# GiGaMega_uneversal_1.net
KiCad netlist of a schematic drawn in EAGLE
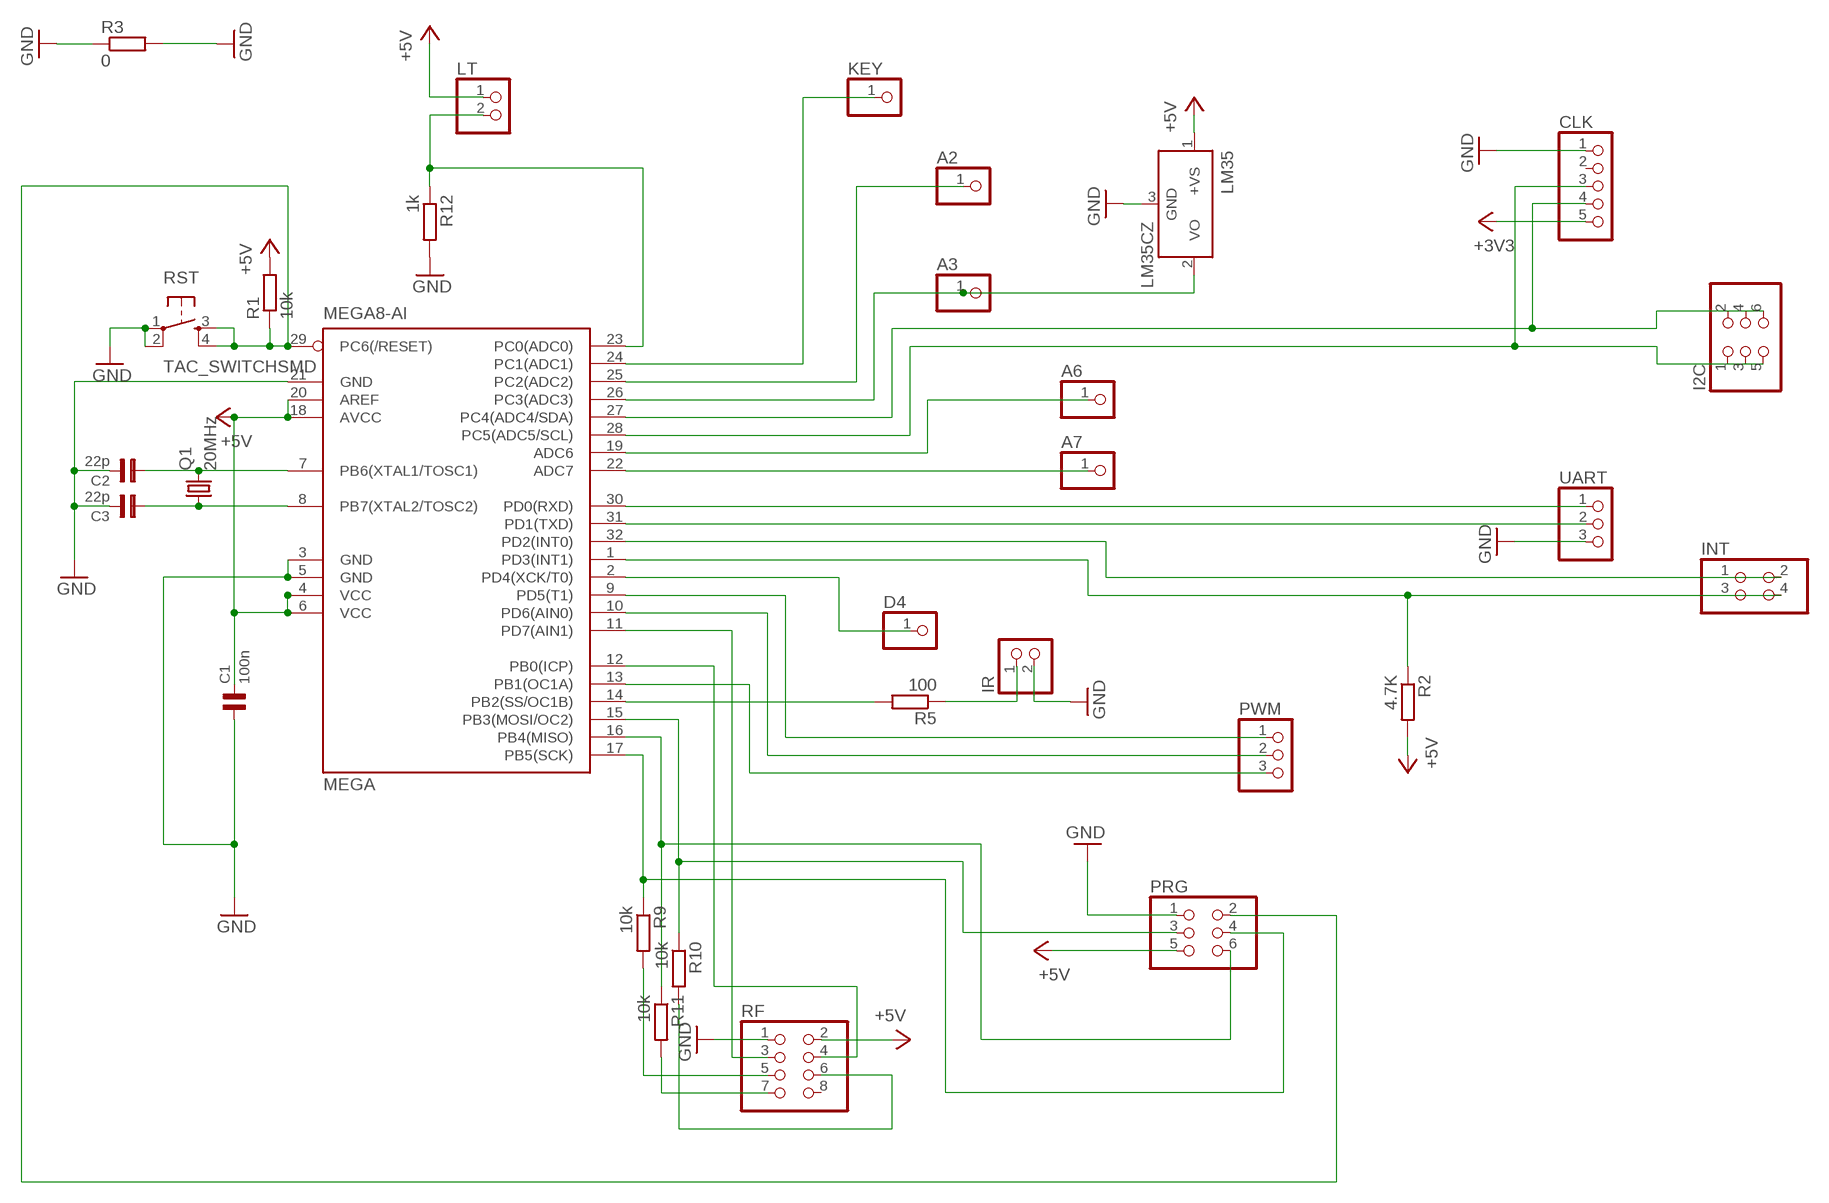
[diagram p0: schematic, sheet 1]
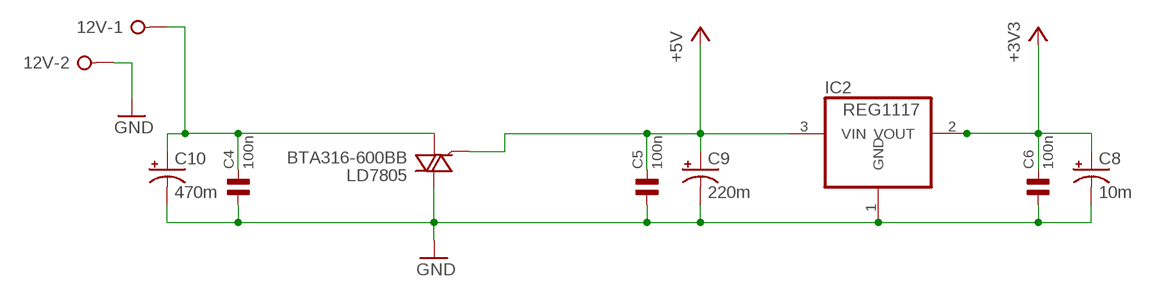
[diagram p1: schematic, sheet 2]

(export (version "E")
  (design (tool "Eeschema 10.0.6"))
  (components
    (comp (ref "12V")
      (value "W237-02P")
      (footprint "eagle-import:W237-132")
      (libsource (lib "eagle-import") (part "W237-02P"))
    )
    (comp (ref "C4")
      (value "100n")
      (footprint "eagle-import:1206")
      (libsource (lib "eagle-import") (part "C1206"))
    )
    (comp (ref "C5")
      (value "100n")
      (footprint "eagle-import:1206")
      (libsource (lib "eagle-import") (part "C1206"))
    )
    (comp (ref "C6")
      (value "100n")
      (footprint "eagle-import:1206")
      (libsource (lib "eagle-import") (part "C1206"))
    )
    (comp (ref "C8")
      (value "10m")
      (footprint "eagle-import:UD-4X5,8_NICHICON")
      (libsource (lib "eagle-import") (part "CPOL-USUD-4X5,8"))
    )
    (comp (ref "C9")
      (value "220m")
      (footprint "eagle-import:UD-6,3X7,7_NICHICON")
      (libsource (lib "eagle-import") (part "CPOL-USUD-6,3X7,7"))
    )
    (comp (ref "C10")
      (value "470m")
      (footprint "eagle-import:UD-10X10_NICHICON")
      (libsource (lib "eagle-import") (part "CPOL-USUD-10X10"))
    )
    (comp (ref "IC2")
      (value "REG1117")
      (footprint "eagle-import:SOT223")
      (libsource (lib "eagle-import") (part "REG1117"))
    )
    (comp (ref "LD7805")
      (value "BTA316-600BB")
      (footprint "eagle-import:SOT404")
      (libsource (lib "eagle-import") (part "BTA316B-600B"))
    )
    (comp (ref "A2")
      (value "PINHD-1X1")
      (footprint "eagle-import:1X01")
      (libsource (lib "eagle-import") (part "PINHD-1X1"))
    )
    (comp (ref "A3")
      (value "PINHD-1X1")
      (footprint "eagle-import:1X01")
      (libsource (lib "eagle-import") (part "PINHD-1X1"))
    )
    (comp (ref "A6")
      (value "PINHD-1X1")
      (footprint "eagle-import:1X01")
      (libsource (lib "eagle-import") (part "PINHD-1X1"))
    )
    (comp (ref "A7")
      (value "PINHD-1X1")
      (footprint "eagle-import:1X01")
      (libsource (lib "eagle-import") (part "PINHD-1X1"))
    )
    (comp (ref "C1")
      (value "100n")
      (footprint "eagle-import:1206")
      (libsource (lib "eagle-import") (part "C1206"))
    )
    (comp (ref "C2")
      (value "22p")
      (footprint "eagle-import:1206")
      (libsource (lib "eagle-import") (part "C1206"))
    )
    (comp (ref "C3")
      (value "22p")
      (footprint "eagle-import:1206")
      (libsource (lib "eagle-import") (part "C1206"))
    )
    (comp (ref "CLK")
      (value "PINHD-1X5")
      (footprint "eagle-import:1X05")
      (libsource (lib "eagle-import") (part "PINHD-1X5"))
    )
    (comp (ref "D4")
      (value "PINHD-1X1")
      (footprint "eagle-import:1X01")
      (libsource (lib "eagle-import") (part "PINHD-1X1"))
    )
    (comp (ref "I2C")
      (value "PINHD-2X3")
      (footprint "eagle-import:2X03")
      (libsource (lib "eagle-import") (part "PINHD-2X3"))
    )
    (comp (ref "INT")
      (value "PINHD-2X2")
      (footprint "eagle-import:2X02")
      (libsource (lib "eagle-import") (part "PINHD-2X2"))
    )
    (comp (ref "IR")
      (value "PINHD-1X2")
      (footprint "eagle-import:1X02")
      (libsource (lib "eagle-import") (part "PINHD-1X2"))
    )
    (comp (ref "KEY")
      (value "PINHD-1X1")
      (footprint "eagle-import:1X01")
      (libsource (lib "eagle-import") (part "PINHD-1X1"))
    )
    (comp (ref "LM35")
      (value "LM35CZ")
      (footprint "eagle-import:TO92")
      (libsource (lib "eagle-import") (part "LM35CZ"))
    )
    (comp (ref "LT")
      (value "PINHD-1X2")
      (footprint "eagle-import:1X02")
      (libsource (lib "eagle-import") (part "PINHD-1X2"))
    )
    (comp (ref "MEGA")
      (value "MEGA8-AI")
      (footprint "eagle-import:TQFP32-08")
      (fields (field (name "MPN") "ATMEGA8-16AU"))
      (libsource (lib "eagle-import") (part "MEGA8-AI"))
    )
    (comp (ref "PRG")
      (value "PINHD-2X3")
      (footprint "eagle-import:2X03")
      (libsource (lib "eagle-import") (part "PINHD-2X3"))
    )
    (comp (ref "PWM")
      (value "PINHD-1X3")
      (footprint "eagle-import:1X03")
      (libsource (lib "eagle-import") (part "PINHD-1X3"))
    )
    (comp (ref "Q1")
      (value "20MHz")
      (footprint "eagle-import:HC49UP")
      (libsource (lib "eagle-import") (part "CRYSTALHC49UP"))
    )
    (comp (ref "R1")
      (value "10k")
      (footprint "eagle-import:R1206")
      (libsource (lib "eagle-import") (part "R-EU_R1206"))
    )
    (comp (ref "R2")
      (value "4.7K")
      (footprint "eagle-import:R1206")
      (libsource (lib "eagle-import") (part "R-EU_R1206"))
    )
    (comp (ref "R3")
      (value "0")
      (footprint "eagle-import:R1206")
      (libsource (lib "eagle-import") (part "R-EU_R1206"))
    )
    (comp (ref "R5")
      (value "100")
      (footprint "eagle-import:R1206")
      (libsource (lib "eagle-import") (part "R-EU_R1206"))
    )
    (comp (ref "R9")
      (value "10k")
      (footprint "eagle-import:R1206")
      (libsource (lib "eagle-import") (part "R-EU_R1206"))
    )
    (comp (ref "R10")
      (value "10k")
      (footprint "eagle-import:R1206")
      (libsource (lib "eagle-import") (part "R-EU_R1206"))
    )
    (comp (ref "R11")
      (value "10k")
      (footprint "eagle-import:R1206")
      (libsource (lib "eagle-import") (part "R-EU_R1206"))
    )
    (comp (ref "R12")
      (value "1k")
      (footprint "eagle-import:R1206")
      (libsource (lib "eagle-import") (part "R-EU_R1206"))
    )
    (comp (ref "RF")
      (value "PINHD-2X4")
      (footprint "eagle-import:2X04")
      (libsource (lib "eagle-import") (part "PINHD-2X4"))
    )
    (comp (ref "RST")
      (value "TAC_SWITCHSMD")
      (footprint "eagle-import:TACTILE-SWITCH-SMD")
      (libsource (lib "eagle-import") (part "TAC_SWITCHSMD"))
    )
    (comp (ref "UART")
      (value "PINHD-1X3")
      (footprint "eagle-import:1X03")
      (libsource (lib "eagle-import") (part "PINHD-1X3"))
    )
  )
  (nets
    (net (code "1") (name "+3V3") (class "Default")
      (node (ref "C6") (pin "2") (pinfunction "2_2") (pintype "passive"))
      (node (ref "C8") (pin "+") (pinfunction "+_+") (pintype "passive"))
      (node (ref "CLK") (pin "5") (pinfunction "5_5") (pintype "passive"))
      (node (ref "IC2") (pin "2") (pinfunction "VOUT_2") (pintype "output"))
    )
    (net (code "2") (name "+5V") (class "Default")
      (node (ref "C1") (pin "2") (pinfunction "2_2") (pintype "passive"))
      (node (ref "C5") (pin "2") (pinfunction "2_2") (pintype "passive"))
      (node (ref "C9") (pin "+") (pinfunction "+_+") (pintype "passive"))
      (node (ref "IC2") (pin "3") (pinfunction "VIN_3") (pintype "input"))
      (node (ref "LD7805") (pin "3") (pinfunction "G_3") (pintype "passive"))
      (node (ref "LM35") (pin "1") (pinfunction "+VS_1") (pintype "input"))
      (node (ref "LT") (pin "1") (pinfunction "1_1") (pintype "passive"))
      (node (ref "MEGA") (pin "18") (pinfunction "AVCC_18") (pintype "power_in"))
      (node (ref "MEGA") (pin "20") (pinfunction "AREF_20") (pintype "passive"))
      (node (ref "MEGA") (pin "4") (pinfunction "VCC_4") (pintype "power_in"))
      (node (ref "MEGA") (pin "6") (pinfunction "VCC_6") (pintype "power_in"))
      (node (ref "PRG") (pin "5") (pinfunction "5_5") (pintype "passive"))
      (node (ref "R1") (pin "2") (pinfunction "2_2") (pintype "passive"))
      (node (ref "R2") (pin "2") (pinfunction "2_2") (pintype "passive"))
      (node (ref "RF") (pin "2") (pinfunction "2_2") (pintype "passive"))
    )
    (net (code "3") (name "GND") (class "Default")
      (node (ref "12V") (pin "2") (pinfunction "KL_2") (pintype "passive"))
      (node (ref "C1") (pin "1") (pinfunction "1_1") (pintype "passive"))
      (node (ref "C10") (pin "-") (pinfunction "-_-") (pintype "passive"))
      (node (ref "C2") (pin "2") (pinfunction "2_2") (pintype "passive"))
      (node (ref "C3") (pin "2") (pinfunction "2_2") (pintype "passive"))
      (node (ref "C4") (pin "1") (pinfunction "1_1") (pintype "passive"))
      (node (ref "C5") (pin "1") (pinfunction "1_1") (pintype "passive"))
      (node (ref "C6") (pin "1") (pinfunction "1_1") (pintype "passive"))
      (node (ref "C8") (pin "-") (pinfunction "-_-") (pintype "passive"))
      (node (ref "C9") (pin "-") (pinfunction "-_-") (pintype "passive"))
      (node (ref "CLK") (pin "1") (pinfunction "1_1") (pintype "passive"))
      (node (ref "IC2") (pin "1") (pinfunction "GND_1") (pintype "power_in"))
      (node (ref "IR") (pin "2") (pinfunction "2_2") (pintype "passive"))
      (node (ref "LD7805") (pin "MB") (pinfunction "LD_MB") (pintype "passive"))
      (node (ref "LM35") (pin "3") (pinfunction "GND_3") (pintype "power_in"))
      (node (ref "MEGA") (pin "21") (pinfunction "GND_21") (pintype "power_in"))
      (node (ref "MEGA") (pin "3") (pinfunction "GND_3") (pintype "power_in"))
      (node (ref "MEGA") (pin "5") (pinfunction "GND_5") (pintype "power_in"))
      (node (ref "PRG") (pin "1") (pinfunction "1_1") (pintype "passive"))
      (node (ref "R12") (pin "2") (pinfunction "2_2") (pintype "passive"))
      (node (ref "R3") (pin "1") (pinfunction "1_1") (pintype "passive"))
      (node (ref "R3") (pin "2") (pinfunction "2_2") (pintype "passive"))
      (node (ref "RF") (pin "1") (pinfunction "1_1") (pintype "passive"))
      (node (ref "RST") (pin "1") (pinfunction "1_1") (pintype "passive"))
      (node (ref "RST") (pin "2") (pinfunction "2_2") (pintype "passive"))
      (node (ref "UART") (pin "3") (pinfunction "3_3") (pintype "passive"))
    )
    (net (code "4") (name "Net-(12VA-KL)") (class "Default")
      (node (ref "12V") (pin "1") (pinfunction "KL_1") (pintype "passive"))
      (node (ref "C10") (pin "+") (pinfunction "+_+") (pintype "passive"))
      (node (ref "C4") (pin "2") (pinfunction "2_2") (pintype "passive"))
      (node (ref "LD7805") (pin "1") (pinfunction "CM_1") (pintype "passive"))
    )
    (net (code "5") (name "Net-(IR-Pad1)") (class "Default")
      (node (ref "IR") (pin "1") (pinfunction "1_1") (pintype "passive"))
      (node (ref "R5") (pin "1") (pinfunction "1_1") (pintype "passive"))
    )
    (net (code "6") (name "Net-(LM35-VO)") (class "Default")
      (node (ref "A3") (pin "1") (pinfunction "1_1") (pintype "passive"))
      (node (ref "LM35") (pin "2") (pinfunction "VO_2") (pintype "input"))
      (node (ref "MEGA") (pin "26") (pinfunction "PC3(ADC3)_26") (pintype "bidirectional"))
    )
    (net (code "7") (name "Net-(MEGA-ADC6)") (class "Default")
      (node (ref "A6") (pin "1") (pinfunction "1_1") (pintype "passive"))
      (node (ref "MEGA") (pin "19") (pinfunction "ADC6_19") (pintype "bidirectional"))
    )
    (net (code "8") (name "Net-(MEGA-ADC7)") (class "Default")
      (node (ref "A7") (pin "1") (pinfunction "1_1") (pintype "passive"))
      (node (ref "MEGA") (pin "22") (pinfunction "ADC7_22") (pintype "bidirectional"))
    )
    (net (code "9") (name "Net-(MEGA-PB0(ICP))") (class "Default")
      (node (ref "MEGA") (pin "12") (pinfunction "PB0(ICP)_12") (pintype "bidirectional"))
      (node (ref "RF") (pin "4") (pinfunction "4_4") (pintype "passive"))
    )
    (net (code "10") (name "Net-(MEGA-PB1(OC1A))") (class "Default")
      (node (ref "MEGA") (pin "13") (pinfunction "PB1(OC1A)_13") (pintype "bidirectional"))
      (node (ref "PWM") (pin "3") (pinfunction "3_3") (pintype "passive"))
    )
    (net (code "11") (name "Net-(MEGA-PB2(SS{slash}OC1B))") (class "Default")
      (node (ref "MEGA") (pin "14") (pinfunction "PB2(SS/OC1B)_14") (pintype "bidirectional"))
      (node (ref "R5") (pin "2") (pinfunction "2_2") (pintype "passive"))
    )
    (net (code "12") (name "Net-(MEGA-PB3(MOSI{slash}OC2))") (class "Default")
      (node (ref "MEGA") (pin "15") (pinfunction "PB3(MOSI/OC2)_15") (pintype "bidirectional"))
      (node (ref "PRG") (pin "3") (pinfunction "3_3") (pintype "passive"))
      (node (ref "R10") (pin "1") (pinfunction "1_1") (pintype "passive"))
    )
    (net (code "13") (name "Net-(MEGA-PB4(MISO))") (class "Default")
      (node (ref "MEGA") (pin "16") (pinfunction "PB4(MISO)_16") (pintype "bidirectional"))
      (node (ref "PRG") (pin "6") (pinfunction "6_6") (pintype "passive"))
      (node (ref "R11") (pin "1") (pinfunction "1_1") (pintype "passive"))
    )
    (net (code "14") (name "Net-(MEGA-PB5(SCK))") (class "Default")
      (node (ref "MEGA") (pin "17") (pinfunction "PB5(SCK)_17") (pintype "bidirectional"))
      (node (ref "PRG") (pin "4") (pinfunction "4_4") (pintype "passive"))
      (node (ref "R9") (pin "1") (pinfunction "1_1") (pintype "passive"))
    )
    (net (code "15") (name "Net-(MEGA-PB6(XTAL1{slash}TOSC1))") (class "Default")
      (node (ref "C2") (pin "1") (pinfunction "1_1") (pintype "passive"))
      (node (ref "MEGA") (pin "7") (pinfunction "PB6(XTAL1/TOSC1)_7") (pintype "bidirectional"))
      (node (ref "Q1") (pin "2") (pinfunction "2_2") (pintype "passive"))
    )
    (net (code "16") (name "Net-(MEGA-PB7(XTAL2{slash}TOSC2))") (class "Default")
      (node (ref "C3") (pin "1") (pinfunction "1_1") (pintype "passive"))
      (node (ref "MEGA") (pin "8") (pinfunction "PB7(XTAL2/TOSC2)_8") (pintype "bidirectional"))
      (node (ref "Q1") (pin "1") (pinfunction "1_1") (pintype "passive"))
    )
    (net (code "17") (name "Net-(MEGA-PC0(ADC0))") (class "Default")
      (node (ref "LT") (pin "2") (pinfunction "2_2") (pintype "passive"))
      (node (ref "MEGA") (pin "23") (pinfunction "PC0(ADC0)_23") (pintype "bidirectional"))
      (node (ref "R12") (pin "1") (pinfunction "1_1") (pintype "passive"))
    )
    (net (code "18") (name "Net-(MEGA-PC1(ADC1))") (class "Default")
      (node (ref "KEY") (pin "1") (pinfunction "1_1") (pintype "passive"))
      (node (ref "MEGA") (pin "24") (pinfunction "PC1(ADC1)_24") (pintype "bidirectional"))
    )
    (net (code "19") (name "Net-(MEGA-PC2(ADC2))") (class "Default")
      (node (ref "A2") (pin "1") (pinfunction "1_1") (pintype "passive"))
      (node (ref "MEGA") (pin "25") (pinfunction "PC2(ADC2)_25") (pintype "bidirectional"))
    )
    (net (code "20") (name "Net-(MEGA-PC4(ADC4{slash}SDA))") (class "Default")
      (node (ref "CLK") (pin "4") (pinfunction "4_4") (pintype "passive"))
      (node (ref "I2C") (pin "2") (pinfunction "2_2") (pintype "passive"))
      (node (ref "I2C") (pin "4") (pinfunction "4_4") (pintype "passive"))
      (node (ref "I2C") (pin "6") (pinfunction "6_6") (pintype "passive"))
      (node (ref "MEGA") (pin "27") (pinfunction "PC4(ADC4/SDA)_27") (pintype "bidirectional"))
    )
    (net (code "21") (name "Net-(MEGA-PC5(ADC5{slash}SCL))") (class "Default")
      (node (ref "CLK") (pin "3") (pinfunction "3_3") (pintype "passive"))
      (node (ref "I2C") (pin "1") (pinfunction "1_1") (pintype "passive"))
      (node (ref "I2C") (pin "3") (pinfunction "3_3") (pintype "passive"))
      (node (ref "I2C") (pin "5") (pinfunction "5_5") (pintype "passive"))
      (node (ref "MEGA") (pin "28") (pinfunction "PC5(ADC5/SCL)_28") (pintype "bidirectional"))
    )
    (net (code "22") (name "Net-(MEGA-PC6({slash}RESET))") (class "Default")
      (node (ref "MEGA") (pin "29") (pinfunction "PC6(/RESET)_29") (pintype "bidirectional"))
      (node (ref "PRG") (pin "2") (pinfunction "2_2") (pintype "passive"))
      (node (ref "R1") (pin "1") (pinfunction "1_1") (pintype "passive"))
      (node (ref "RST") (pin "3") (pinfunction "3_3") (pintype "passive"))
      (node (ref "RST") (pin "4") (pinfunction "4_4") (pintype "passive"))
    )
    (net (code "23") (name "Net-(MEGA-PD0(RXD))") (class "Default")
      (node (ref "MEGA") (pin "30") (pinfunction "PD0(RXD)_30") (pintype "bidirectional"))
      (node (ref "UART") (pin "1") (pinfunction "1_1") (pintype "passive"))
    )
    (net (code "24") (name "Net-(MEGA-PD1(TXD))") (class "Default")
      (node (ref "MEGA") (pin "31") (pinfunction "PD1(TXD)_31") (pintype "bidirectional"))
      (node (ref "UART") (pin "2") (pinfunction "2_2") (pintype "passive"))
    )
    (net (code "25") (name "Net-(MEGA-PD2(INT0))") (class "Default")
      (node (ref "INT") (pin "1") (pinfunction "1_1") (pintype "passive"))
      (node (ref "INT") (pin "2") (pinfunction "2_2") (pintype "passive"))
      (node (ref "MEGA") (pin "32") (pinfunction "PD2(INT0)_32") (pintype "bidirectional"))
    )
    (net (code "26") (name "Net-(MEGA-PD3(INT1))") (class "Default")
      (node (ref "INT") (pin "3") (pinfunction "3_3") (pintype "passive"))
      (node (ref "INT") (pin "4") (pinfunction "4_4") (pintype "passive"))
      (node (ref "MEGA") (pin "1") (pinfunction "PD3(INT1)_1") (pintype "bidirectional"))
      (node (ref "R2") (pin "1") (pinfunction "1_1") (pintype "passive"))
    )
    (net (code "27") (name "Net-(MEGA-PD4(XCK{slash}T0))") (class "Default")
      (node (ref "D4") (pin "1") (pinfunction "1_1") (pintype "passive"))
      (node (ref "MEGA") (pin "2") (pinfunction "PD4(XCK/T0)_2") (pintype "bidirectional"))
    )
    (net (code "28") (name "Net-(MEGA-PD5(T1))") (class "Default")
      (node (ref "MEGA") (pin "9") (pinfunction "PD5(T1)_9") (pintype "bidirectional"))
      (node (ref "PWM") (pin "1") (pinfunction "1_1") (pintype "passive"))
    )
    (net (code "29") (name "Net-(MEGA-PD6(AIN0))") (class "Default")
      (node (ref "MEGA") (pin "10") (pinfunction "PD6(AIN0)_10") (pintype "bidirectional"))
      (node (ref "PWM") (pin "2") (pinfunction "2_2") (pintype "passive"))
    )
    (net (code "30") (name "Net-(MEGA-PD7(AIN1))") (class "Default")
      (node (ref "MEGA") (pin "11") (pinfunction "PD7(AIN1)_11") (pintype "bidirectional"))
      (node (ref "RF") (pin "3") (pinfunction "3_3") (pintype "passive"))
    )
    (net (code "31") (name "Net-(R9-Pad2)") (class "Default")
      (node (ref "R9") (pin "2") (pinfunction "2_2") (pintype "passive"))
      (node (ref "RF") (pin "5") (pinfunction "5_5") (pintype "passive"))
    )
    (net (code "32") (name "Net-(R10-Pad2)") (class "Default")
      (node (ref "R10") (pin "2") (pinfunction "2_2") (pintype "passive"))
      (node (ref "RF") (pin "6") (pinfunction "6_6") (pintype "passive"))
    )
    (net (code "33") (name "Net-(R11-Pad2)") (class "Default")
      (node (ref "R11") (pin "2") (pinfunction "2_2") (pintype "passive"))
      (node (ref "RF") (pin "7") (pinfunction "7_7") (pintype "passive"))
    )
    (net (code "34") (name "unconnected-(CLK-Pad2)") (class "Default")
      (node (ref "CLK") (pin "2") (pinfunction "2_2") (pintype "passive"))
    )
    (net (code "35") (name "unconnected-(RF-Pad8)") (class "Default")
      (node (ref "RF") (pin "8") (pinfunction "8_8") (pintype "passive"))
    )
  )
)
